# Logic_Engine_-_Front_SK6812.net
KiCad netlist of a schematic drawn in EAGLE
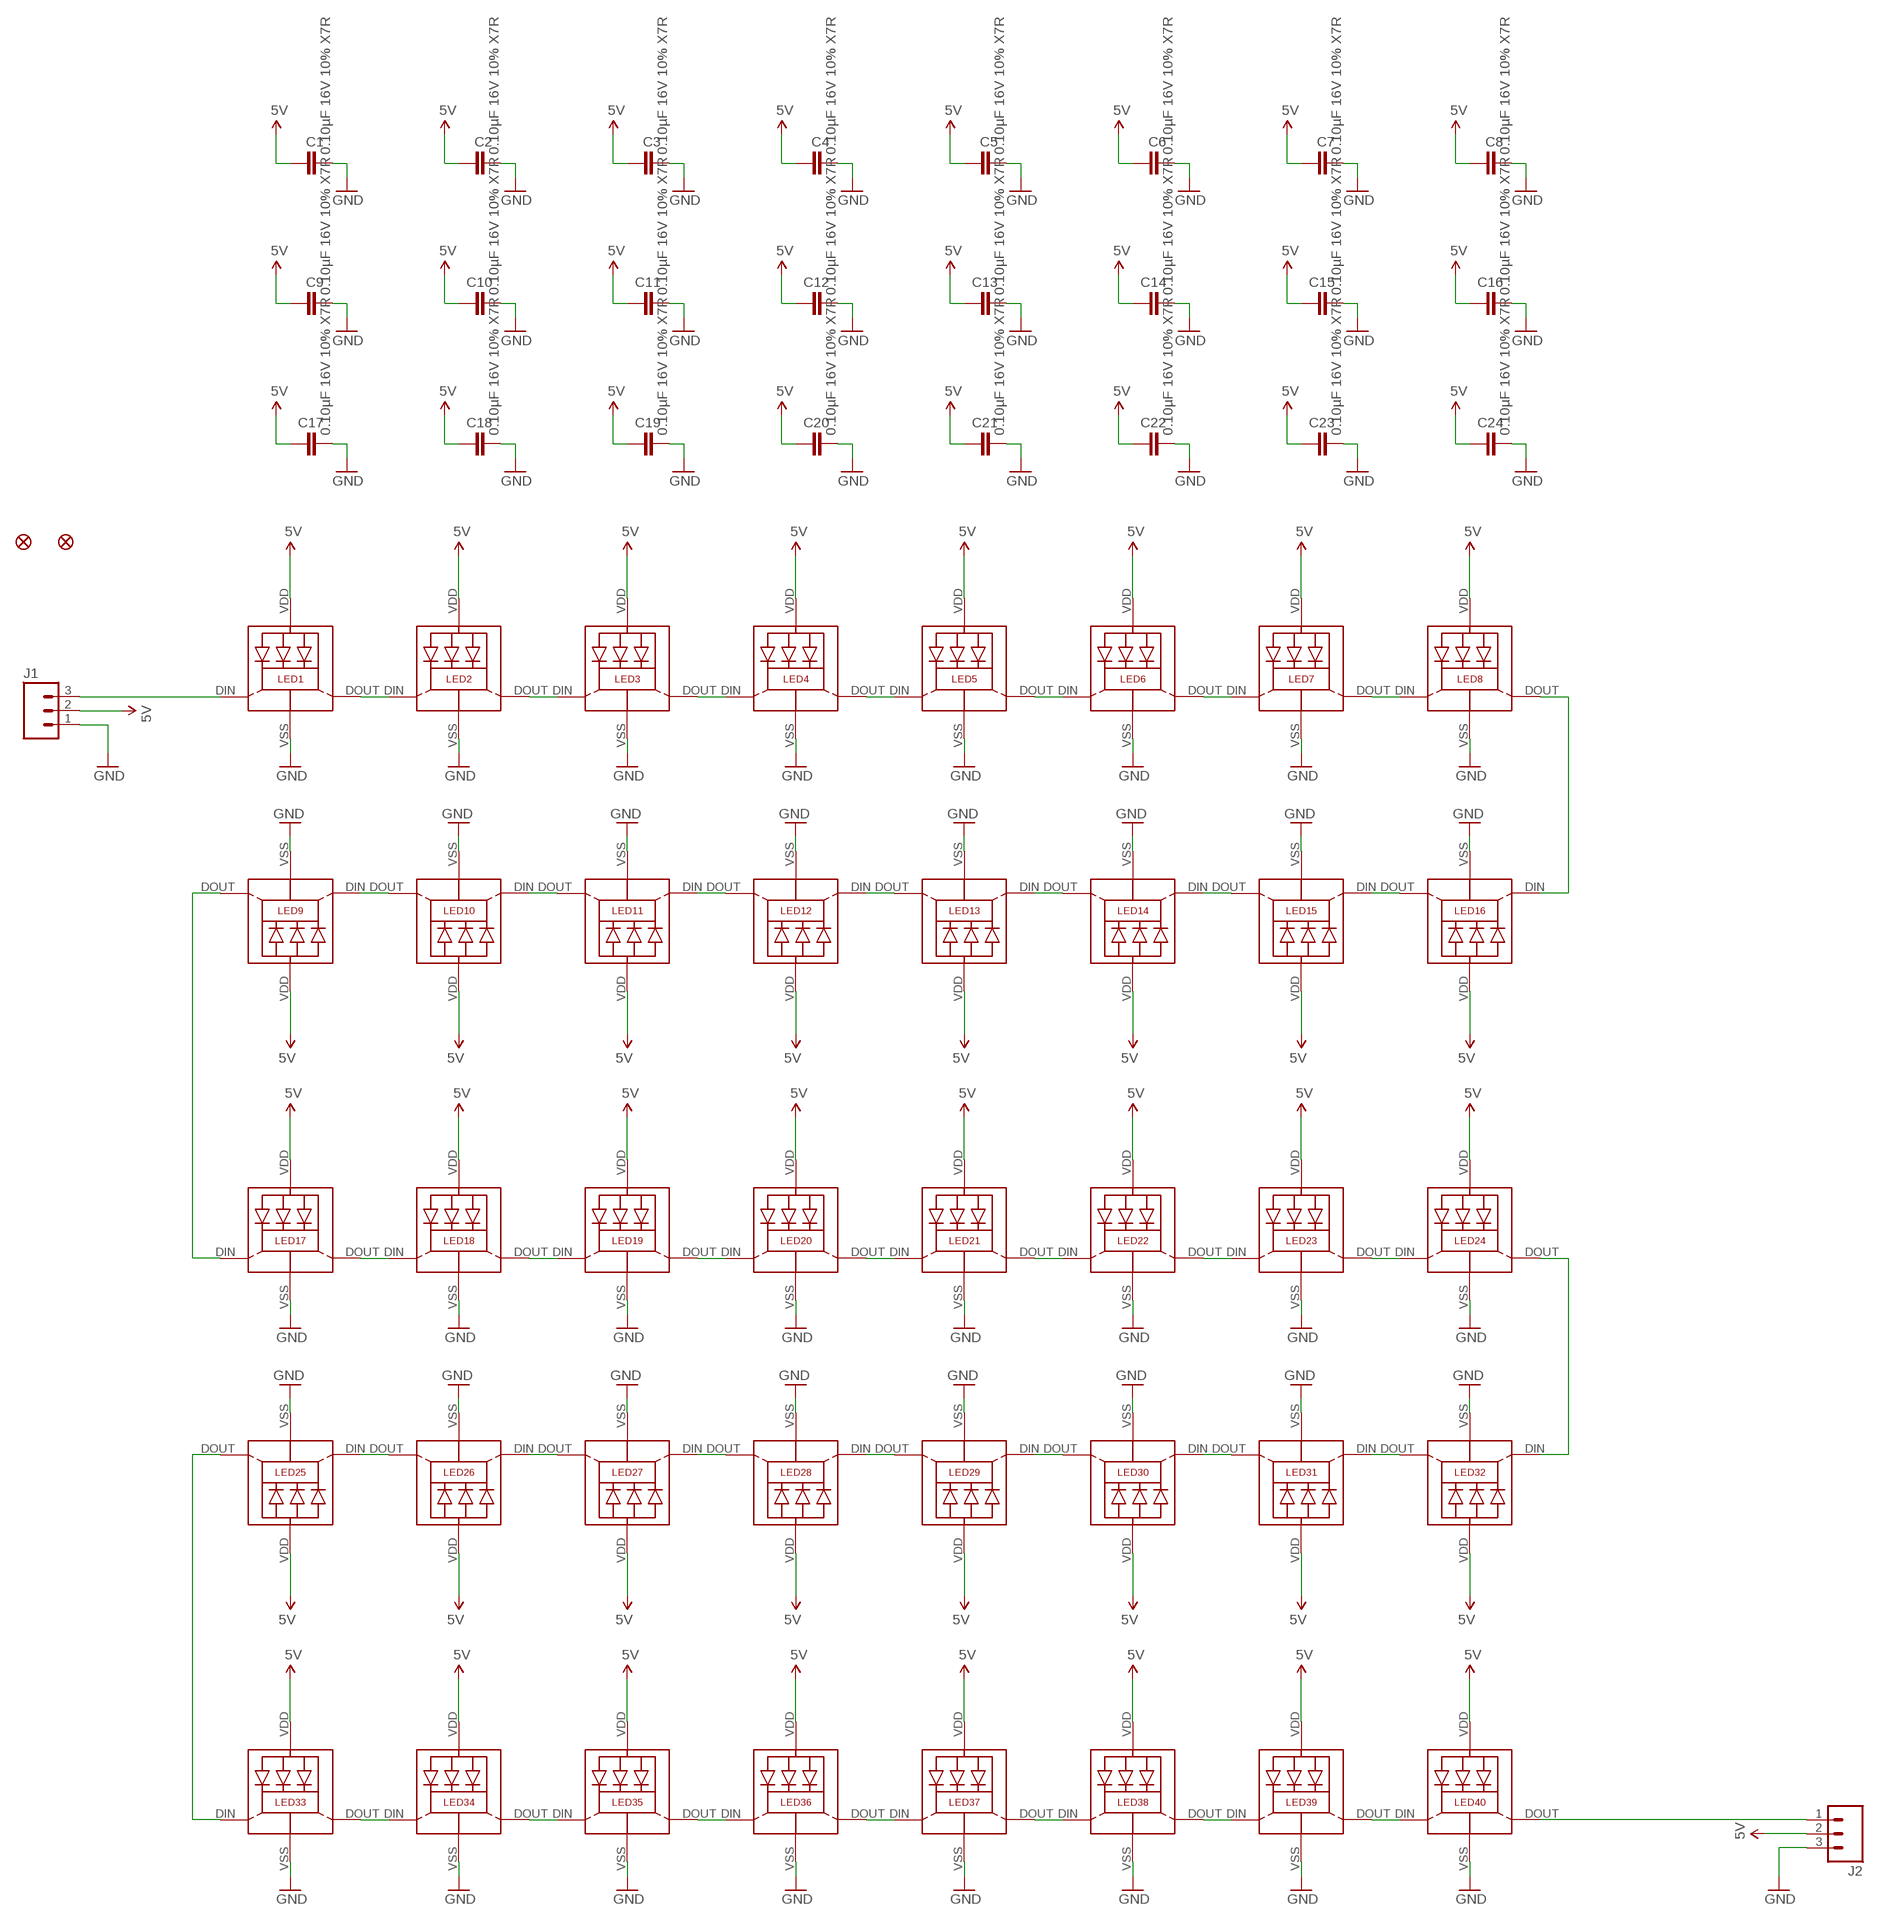
[diagram p0: schematic, sheet 1]

(export (version "E")
  (design (tool "Eeschema 10.0.6"))
  (components
    (comp (ref "C1")
      (value "0.10µF 16V 10% X7R")
      (footprint "eagle-import:C0603")
      (libsource (lib "eagle-import") (part "C-EUC0603"))
    )
    (comp (ref "C2")
      (value "0.10µF 16V 10% X7R")
      (footprint "eagle-import:C0603")
      (libsource (lib "eagle-import") (part "C-EUC0603"))
    )
    (comp (ref "C3")
      (value "0.10µF 16V 10% X7R")
      (footprint "eagle-import:C0603")
      (libsource (lib "eagle-import") (part "C-EUC0603"))
    )
    (comp (ref "C4")
      (value "0.10µF 16V 10% X7R")
      (footprint "eagle-import:C0603")
      (libsource (lib "eagle-import") (part "C-EUC0603"))
    )
    (comp (ref "C5")
      (value "0.10µF 16V 10% X7R")
      (footprint "eagle-import:C0603")
      (libsource (lib "eagle-import") (part "C-EUC0603"))
    )
    (comp (ref "C6")
      (value "0.10µF 16V 10% X7R")
      (footprint "eagle-import:C0603")
      (libsource (lib "eagle-import") (part "C-EUC0603"))
    )
    (comp (ref "C7")
      (value "0.10µF 16V 10% X7R")
      (footprint "eagle-import:C0603")
      (libsource (lib "eagle-import") (part "C-EUC0603"))
    )
    (comp (ref "C8")
      (value "0.10µF 16V 10% X7R")
      (footprint "eagle-import:C0603")
      (libsource (lib "eagle-import") (part "C-EUC0603"))
    )
    (comp (ref "C9")
      (value "0.10µF 16V 10% X7R")
      (footprint "eagle-import:C0603")
      (libsource (lib "eagle-import") (part "C-EUC0603"))
    )
    (comp (ref "C10")
      (value "0.10µF 16V 10% X7R")
      (footprint "eagle-import:C0603")
      (libsource (lib "eagle-import") (part "C-EUC0603"))
    )
    (comp (ref "C11")
      (value "0.10µF 16V 10% X7R")
      (footprint "eagle-import:C0603")
      (libsource (lib "eagle-import") (part "C-EUC0603"))
    )
    (comp (ref "C12")
      (value "0.10µF 16V 10% X7R")
      (footprint "eagle-import:C0603")
      (libsource (lib "eagle-import") (part "C-EUC0603"))
    )
    (comp (ref "C13")
      (value "0.10µF 16V 10% X7R")
      (footprint "eagle-import:C0603")
      (libsource (lib "eagle-import") (part "C-EUC0603"))
    )
    (comp (ref "C14")
      (value "0.10µF 16V 10% X7R")
      (footprint "eagle-import:C0603")
      (libsource (lib "eagle-import") (part "C-EUC0603"))
    )
    (comp (ref "C15")
      (value "0.10µF 16V 10% X7R")
      (footprint "eagle-import:C0603")
      (libsource (lib "eagle-import") (part "C-EUC0603"))
    )
    (comp (ref "C16")
      (value "0.10µF 16V 10% X7R")
      (footprint "eagle-import:C0603")
      (libsource (lib "eagle-import") (part "C-EUC0603"))
    )
    (comp (ref "C17")
      (value "0.10µF 16V 10% X7R")
      (footprint "eagle-import:C0603")
      (libsource (lib "eagle-import") (part "C-EUC0603"))
    )
    (comp (ref "C18")
      (value "0.10µF 16V 10% X7R")
      (footprint "eagle-import:C0603")
      (libsource (lib "eagle-import") (part "C-EUC0603"))
    )
    (comp (ref "C19")
      (value "0.10µF 16V 10% X7R")
      (footprint "eagle-import:C0603")
      (libsource (lib "eagle-import") (part "C-EUC0603"))
    )
    (comp (ref "C20")
      (value "0.10µF 16V 10% X7R")
      (footprint "eagle-import:C0603")
      (libsource (lib "eagle-import") (part "C-EUC0603"))
    )
    (comp (ref "C21")
      (value "0.10µF 16V 10% X7R")
      (footprint "eagle-import:C0603")
      (libsource (lib "eagle-import") (part "C-EUC0603"))
    )
    (comp (ref "C22")
      (value "0.10µF 16V 10% X7R")
      (footprint "eagle-import:C0603")
      (libsource (lib "eagle-import") (part "C-EUC0603"))
    )
    (comp (ref "C23")
      (value "0.10µF 16V 10% X7R")
      (footprint "eagle-import:C0603")
      (libsource (lib "eagle-import") (part "C-EUC0603"))
    )
    (comp (ref "C24")
      (value "0.10µF 16V 10% X7R")
      (footprint "eagle-import:C0603")
      (libsource (lib "eagle-import") (part "C-EUC0603"))
    )
    (comp (ref "FD1")
      (value "FIDUCIAL1X2")
      (footprint "eagle-import:FIDUCIAL-1X2")
      (libsource (lib "eagle-import") (part "FIDUCIAL1X2"))
    )
    (comp (ref "FD2")
      (value "FIDUCIAL1X2")
      (footprint "eagle-import:FIDUCIAL-1X2")
      (libsource (lib "eagle-import") (part "FIDUCIAL1X2"))
    )
    (comp (ref "J1")
      (value "M03PTH")
      (footprint "eagle-import:1X03")
      (libsource (lib "eagle-import") (part "M03PTH"))
    )
    (comp (ref "J2")
      (value "M03PTH")
      (footprint "eagle-import:1X03")
      (libsource (lib "eagle-import") (part "M03PTH"))
    )
    (comp (ref "LED1")
      (value "WS2812BSK6812MINI")
      (footprint "eagle-import:SK6812MINI")
      (libsource (lib "eagle-import") (part "WS2812BSK6812MINI"))
    )
    (comp (ref "LED2")
      (value "WS2812BSK6812MINI")
      (footprint "eagle-import:SK6812MINI")
      (libsource (lib "eagle-import") (part "WS2812BSK6812MINI"))
    )
    (comp (ref "LED3")
      (value "WS2812BSK6812MINI")
      (footprint "eagle-import:SK6812MINI")
      (libsource (lib "eagle-import") (part "WS2812BSK6812MINI"))
    )
    (comp (ref "LED4")
      (value "WS2812BSK6812MINI")
      (footprint "eagle-import:SK6812MINI")
      (libsource (lib "eagle-import") (part "WS2812BSK6812MINI"))
    )
    (comp (ref "LED5")
      (value "WS2812BSK6812MINI")
      (footprint "eagle-import:SK6812MINI")
      (libsource (lib "eagle-import") (part "WS2812BSK6812MINI"))
    )
    (comp (ref "LED6")
      (value "WS2812BSK6812MINI")
      (footprint "eagle-import:SK6812MINI")
      (libsource (lib "eagle-import") (part "WS2812BSK6812MINI"))
    )
    (comp (ref "LED7")
      (value "WS2812BSK6812MINI")
      (footprint "eagle-import:SK6812MINI")
      (libsource (lib "eagle-import") (part "WS2812BSK6812MINI"))
    )
    (comp (ref "LED8")
      (value "WS2812BSK6812MINI")
      (footprint "eagle-import:SK6812MINI")
      (libsource (lib "eagle-import") (part "WS2812BSK6812MINI"))
    )
    (comp (ref "LED9")
      (value "WS2812BSK6812MINI")
      (footprint "eagle-import:SK6812MINI")
      (libsource (lib "eagle-import") (part "WS2812BSK6812MINI"))
    )
    (comp (ref "LED10")
      (value "WS2812BSK6812MINI")
      (footprint "eagle-import:SK6812MINI")
      (libsource (lib "eagle-import") (part "WS2812BSK6812MINI"))
    )
    (comp (ref "LED11")
      (value "WS2812BSK6812MINI")
      (footprint "eagle-import:SK6812MINI")
      (libsource (lib "eagle-import") (part "WS2812BSK6812MINI"))
    )
    (comp (ref "LED12")
      (value "WS2812BSK6812MINI")
      (footprint "eagle-import:SK6812MINI")
      (libsource (lib "eagle-import") (part "WS2812BSK6812MINI"))
    )
    (comp (ref "LED13")
      (value "WS2812BSK6812MINI")
      (footprint "eagle-import:SK6812MINI")
      (libsource (lib "eagle-import") (part "WS2812BSK6812MINI"))
    )
    (comp (ref "LED14")
      (value "WS2812BSK6812MINI")
      (footprint "eagle-import:SK6812MINI")
      (libsource (lib "eagle-import") (part "WS2812BSK6812MINI"))
    )
    (comp (ref "LED15")
      (value "WS2812BSK6812MINI")
      (footprint "eagle-import:SK6812MINI")
      (libsource (lib "eagle-import") (part "WS2812BSK6812MINI"))
    )
    (comp (ref "LED16")
      (value "WS2812BSK6812MINI")
      (footprint "eagle-import:SK6812MINI")
      (libsource (lib "eagle-import") (part "WS2812BSK6812MINI"))
    )
    (comp (ref "LED17")
      (value "WS2812BSK6812MINI")
      (footprint "eagle-import:SK6812MINI")
      (libsource (lib "eagle-import") (part "WS2812BSK6812MINI"))
    )
    (comp (ref "LED18")
      (value "WS2812BSK6812MINI")
      (footprint "eagle-import:SK6812MINI")
      (libsource (lib "eagle-import") (part "WS2812BSK6812MINI"))
    )
    (comp (ref "LED19")
      (value "WS2812BSK6812MINI")
      (footprint "eagle-import:SK6812MINI")
      (libsource (lib "eagle-import") (part "WS2812BSK6812MINI"))
    )
    (comp (ref "LED20")
      (value "WS2812BSK6812MINI")
      (footprint "eagle-import:SK6812MINI")
      (libsource (lib "eagle-import") (part "WS2812BSK6812MINI"))
    )
    (comp (ref "LED21")
      (value "WS2812BSK6812MINI")
      (footprint "eagle-import:SK6812MINI")
      (libsource (lib "eagle-import") (part "WS2812BSK6812MINI"))
    )
    (comp (ref "LED22")
      (value "WS2812BSK6812MINI")
      (footprint "eagle-import:SK6812MINI")
      (libsource (lib "eagle-import") (part "WS2812BSK6812MINI"))
    )
    (comp (ref "LED23")
      (value "WS2812BSK6812MINI")
      (footprint "eagle-import:SK6812MINI")
      (libsource (lib "eagle-import") (part "WS2812BSK6812MINI"))
    )
    (comp (ref "LED24")
      (value "WS2812BSK6812MINI")
      (footprint "eagle-import:SK6812MINI")
      (libsource (lib "eagle-import") (part "WS2812BSK6812MINI"))
    )
    (comp (ref "LED25")
      (value "WS2812BSK6812MINI")
      (footprint "eagle-import:SK6812MINI")
      (libsource (lib "eagle-import") (part "WS2812BSK6812MINI"))
    )
    (comp (ref "LED26")
      (value "WS2812BSK6812MINI")
      (footprint "eagle-import:SK6812MINI")
      (libsource (lib "eagle-import") (part "WS2812BSK6812MINI"))
    )
    (comp (ref "LED27")
      (value "WS2812BSK6812MINI")
      (footprint "eagle-import:SK6812MINI")
      (libsource (lib "eagle-import") (part "WS2812BSK6812MINI"))
    )
    (comp (ref "LED28")
      (value "WS2812BSK6812MINI")
      (footprint "eagle-import:SK6812MINI")
      (libsource (lib "eagle-import") (part "WS2812BSK6812MINI"))
    )
    (comp (ref "LED29")
      (value "WS2812BSK6812MINI")
      (footprint "eagle-import:SK6812MINI")
      (libsource (lib "eagle-import") (part "WS2812BSK6812MINI"))
    )
    (comp (ref "LED30")
      (value "WS2812BSK6812MINI")
      (footprint "eagle-import:SK6812MINI")
      (libsource (lib "eagle-import") (part "WS2812BSK6812MINI"))
    )
    (comp (ref "LED31")
      (value "WS2812BSK6812MINI")
      (footprint "eagle-import:SK6812MINI")
      (libsource (lib "eagle-import") (part "WS2812BSK6812MINI"))
    )
    (comp (ref "LED32")
      (value "WS2812BSK6812MINI")
      (footprint "eagle-import:SK6812MINI")
      (libsource (lib "eagle-import") (part "WS2812BSK6812MINI"))
    )
    (comp (ref "LED33")
      (value "WS2812BSK6812MINI")
      (footprint "eagle-import:SK6812MINI")
      (libsource (lib "eagle-import") (part "WS2812BSK6812MINI"))
    )
    (comp (ref "LED34")
      (value "WS2812BSK6812MINI")
      (footprint "eagle-import:SK6812MINI")
      (libsource (lib "eagle-import") (part "WS2812BSK6812MINI"))
    )
    (comp (ref "LED35")
      (value "WS2812BSK6812MINI")
      (footprint "eagle-import:SK6812MINI")
      (libsource (lib "eagle-import") (part "WS2812BSK6812MINI"))
    )
    (comp (ref "LED36")
      (value "WS2812BSK6812MINI")
      (footprint "eagle-import:SK6812MINI")
      (libsource (lib "eagle-import") (part "WS2812BSK6812MINI"))
    )
    (comp (ref "LED37")
      (value "WS2812BSK6812MINI")
      (footprint "eagle-import:SK6812MINI")
      (libsource (lib "eagle-import") (part "WS2812BSK6812MINI"))
    )
    (comp (ref "LED38")
      (value "WS2812BSK6812MINI")
      (footprint "eagle-import:SK6812MINI")
      (libsource (lib "eagle-import") (part "WS2812BSK6812MINI"))
    )
    (comp (ref "LED39")
      (value "WS2812BSK6812MINI")
      (footprint "eagle-import:SK6812MINI")
      (libsource (lib "eagle-import") (part "WS2812BSK6812MINI"))
    )
    (comp (ref "LED40")
      (value "WS2812BSK6812MINI")
      (footprint "eagle-import:SK6812MINI")
      (libsource (lib "eagle-import") (part "WS2812BSK6812MINI"))
    )
  )
  (nets
    (net (code "1") (name "5V") (class "Default")
      (node (ref "C1") (pin "1") (pinfunction "1_1") (pintype "passive"))
      (node (ref "C10") (pin "1") (pinfunction "1_1") (pintype "passive"))
      (node (ref "C11") (pin "1") (pinfunction "1_1") (pintype "passive"))
      (node (ref "C12") (pin "1") (pinfunction "1_1") (pintype "passive"))
      (node (ref "C13") (pin "1") (pinfunction "1_1") (pintype "passive"))
      (node (ref "C14") (pin "1") (pinfunction "1_1") (pintype "passive"))
      (node (ref "C15") (pin "1") (pinfunction "1_1") (pintype "passive"))
      (node (ref "C16") (pin "1") (pinfunction "1_1") (pintype "passive"))
      (node (ref "C17") (pin "1") (pinfunction "1_1") (pintype "passive"))
      (node (ref "C18") (pin "1") (pinfunction "1_1") (pintype "passive"))
      (node (ref "C19") (pin "1") (pinfunction "1_1") (pintype "passive"))
      (node (ref "C2") (pin "1") (pinfunction "1_1") (pintype "passive"))
      (node (ref "C20") (pin "1") (pinfunction "1_1") (pintype "passive"))
      (node (ref "C21") (pin "1") (pinfunction "1_1") (pintype "passive"))
      (node (ref "C22") (pin "1") (pinfunction "1_1") (pintype "passive"))
      (node (ref "C23") (pin "1") (pinfunction "1_1") (pintype "passive"))
      (node (ref "C24") (pin "1") (pinfunction "1_1") (pintype "passive"))
      (node (ref "C3") (pin "1") (pinfunction "1_1") (pintype "passive"))
      (node (ref "C4") (pin "1") (pinfunction "1_1") (pintype "passive"))
      (node (ref "C5") (pin "1") (pinfunction "1_1") (pintype "passive"))
      (node (ref "C6") (pin "1") (pinfunction "1_1") (pintype "passive"))
      (node (ref "C7") (pin "1") (pinfunction "1_1") (pintype "passive"))
      (node (ref "C8") (pin "1") (pinfunction "1_1") (pintype "passive"))
      (node (ref "C9") (pin "1") (pinfunction "1_1") (pintype "passive"))
      (node (ref "J1") (pin "2") (pinfunction "2_2") (pintype "passive"))
      (node (ref "J2") (pin "2") (pinfunction "2_2") (pintype "passive"))
      (node (ref "LED1") (pin "VDD") (pinfunction "VDD_VDD") (pintype "power_in"))
      (node (ref "LED10") (pin "VDD") (pinfunction "VDD_VDD") (pintype "power_in"))
      (node (ref "LED11") (pin "VDD") (pinfunction "VDD_VDD") (pintype "power_in"))
      (node (ref "LED12") (pin "VDD") (pinfunction "VDD_VDD") (pintype "power_in"))
      (node (ref "LED13") (pin "VDD") (pinfunction "VDD_VDD") (pintype "power_in"))
      (node (ref "LED14") (pin "VDD") (pinfunction "VDD_VDD") (pintype "power_in"))
      (node (ref "LED15") (pin "VDD") (pinfunction "VDD_VDD") (pintype "power_in"))
      (node (ref "LED16") (pin "VDD") (pinfunction "VDD_VDD") (pintype "power_in"))
      (node (ref "LED17") (pin "VDD") (pinfunction "VDD_VDD") (pintype "power_in"))
      (node (ref "LED18") (pin "VDD") (pinfunction "VDD_VDD") (pintype "power_in"))
      (node (ref "LED19") (pin "VDD") (pinfunction "VDD_VDD") (pintype "power_in"))
      (node (ref "LED2") (pin "VDD") (pinfunction "VDD_VDD") (pintype "power_in"))
      (node (ref "LED20") (pin "VDD") (pinfunction "VDD_VDD") (pintype "power_in"))
      (node (ref "LED21") (pin "VDD") (pinfunction "VDD_VDD") (pintype "power_in"))
      (node (ref "LED22") (pin "VDD") (pinfunction "VDD_VDD") (pintype "power_in"))
      (node (ref "LED23") (pin "VDD") (pinfunction "VDD_VDD") (pintype "power_in"))
      (node (ref "LED24") (pin "VDD") (pinfunction "VDD_VDD") (pintype "power_in"))
      (node (ref "LED25") (pin "VDD") (pinfunction "VDD_VDD") (pintype "power_in"))
      (node (ref "LED26") (pin "VDD") (pinfunction "VDD_VDD") (pintype "power_in"))
      (node (ref "LED27") (pin "VDD") (pinfunction "VDD_VDD") (pintype "power_in"))
      (node (ref "LED28") (pin "VDD") (pinfunction "VDD_VDD") (pintype "power_in"))
      (node (ref "LED29") (pin "VDD") (pinfunction "VDD_VDD") (pintype "power_in"))
      (node (ref "LED3") (pin "VDD") (pinfunction "VDD_VDD") (pintype "power_in"))
      (node (ref "LED30") (pin "VDD") (pinfunction "VDD_VDD") (pintype "power_in"))
      (node (ref "LED31") (pin "VDD") (pinfunction "VDD_VDD") (pintype "power_in"))
      (node (ref "LED32") (pin "VDD") (pinfunction "VDD_VDD") (pintype "power_in"))
      (node (ref "LED33") (pin "VDD") (pinfunction "VDD_VDD") (pintype "power_in"))
      (node (ref "LED34") (pin "VDD") (pinfunction "VDD_VDD") (pintype "power_in"))
      (node (ref "LED35") (pin "VDD") (pinfunction "VDD_VDD") (pintype "power_in"))
      (node (ref "LED36") (pin "VDD") (pinfunction "VDD_VDD") (pintype "power_in"))
      (node (ref "LED37") (pin "VDD") (pinfunction "VDD_VDD") (pintype "power_in"))
      (node (ref "LED38") (pin "VDD") (pinfunction "VDD_VDD") (pintype "power_in"))
      (node (ref "LED39") (pin "VDD") (pinfunction "VDD_VDD") (pintype "power_in"))
      (node (ref "LED4") (pin "VDD") (pinfunction "VDD_VDD") (pintype "power_in"))
      (node (ref "LED40") (pin "VDD") (pinfunction "VDD_VDD") (pintype "power_in"))
      (node (ref "LED5") (pin "VDD") (pinfunction "VDD_VDD") (pintype "power_in"))
      (node (ref "LED6") (pin "VDD") (pinfunction "VDD_VDD") (pintype "power_in"))
      (node (ref "LED7") (pin "VDD") (pinfunction "VDD_VDD") (pintype "power_in"))
      (node (ref "LED8") (pin "VDD") (pinfunction "VDD_VDD") (pintype "power_in"))
      (node (ref "LED9") (pin "VDD") (pinfunction "VDD_VDD") (pintype "power_in"))
    )
    (net (code "2") (name "GND") (class "Default")
      (node (ref "C1") (pin "2") (pinfunction "2_2") (pintype "passive"))
      (node (ref "C10") (pin "2") (pinfunction "2_2") (pintype "passive"))
      (node (ref "C11") (pin "2") (pinfunction "2_2") (pintype "passive"))
      (node (ref "C12") (pin "2") (pinfunction "2_2") (pintype "passive"))
      (node (ref "C13") (pin "2") (pinfunction "2_2") (pintype "passive"))
      (node (ref "C14") (pin "2") (pinfunction "2_2") (pintype "passive"))
      (node (ref "C15") (pin "2") (pinfunction "2_2") (pintype "passive"))
      (node (ref "C16") (pin "2") (pinfunction "2_2") (pintype "passive"))
      (node (ref "C17") (pin "2") (pinfunction "2_2") (pintype "passive"))
      (node (ref "C18") (pin "2") (pinfunction "2_2") (pintype "passive"))
      (node (ref "C19") (pin "2") (pinfunction "2_2") (pintype "passive"))
      (node (ref "C2") (pin "2") (pinfunction "2_2") (pintype "passive"))
      (node (ref "C20") (pin "2") (pinfunction "2_2") (pintype "passive"))
      (node (ref "C21") (pin "2") (pinfunction "2_2") (pintype "passive"))
      (node (ref "C22") (pin "2") (pinfunction "2_2") (pintype "passive"))
      (node (ref "C23") (pin "2") (pinfunction "2_2") (pintype "passive"))
      (node (ref "C24") (pin "2") (pinfunction "2_2") (pintype "passive"))
      (node (ref "C3") (pin "2") (pinfunction "2_2") (pintype "passive"))
      (node (ref "C4") (pin "2") (pinfunction "2_2") (pintype "passive"))
      (node (ref "C5") (pin "2") (pinfunction "2_2") (pintype "passive"))
      (node (ref "C6") (pin "2") (pinfunction "2_2") (pintype "passive"))
      (node (ref "C7") (pin "2") (pinfunction "2_2") (pintype "passive"))
      (node (ref "C8") (pin "2") (pinfunction "2_2") (pintype "passive"))
      (node (ref "C9") (pin "2") (pinfunction "2_2") (pintype "passive"))
      (node (ref "J1") (pin "1") (pinfunction "1_1") (pintype "passive"))
      (node (ref "J2") (pin "3") (pinfunction "3_3") (pintype "passive"))
      (node (ref "LED1") (pin "VSS") (pinfunction "GND_VSS") (pintype "power_in"))
      (node (ref "LED10") (pin "VSS") (pinfunction "GND_VSS") (pintype "power_in"))
      (node (ref "LED11") (pin "VSS") (pinfunction "GND_VSS") (pintype "power_in"))
      (node (ref "LED12") (pin "VSS") (pinfunction "GND_VSS") (pintype "power_in"))
      (node (ref "LED13") (pin "VSS") (pinfunction "GND_VSS") (pintype "power_in"))
      (node (ref "LED14") (pin "VSS") (pinfunction "GND_VSS") (pintype "power_in"))
      (node (ref "LED15") (pin "VSS") (pinfunction "GND_VSS") (pintype "power_in"))
      (node (ref "LED16") (pin "VSS") (pinfunction "GND_VSS") (pintype "power_in"))
      (node (ref "LED17") (pin "VSS") (pinfunction "GND_VSS") (pintype "power_in"))
      (node (ref "LED18") (pin "VSS") (pinfunction "GND_VSS") (pintype "power_in"))
      (node (ref "LED19") (pin "VSS") (pinfunction "GND_VSS") (pintype "power_in"))
      (node (ref "LED2") (pin "VSS") (pinfunction "GND_VSS") (pintype "power_in"))
      (node (ref "LED20") (pin "VSS") (pinfunction "GND_VSS") (pintype "power_in"))
      (node (ref "LED21") (pin "VSS") (pinfunction "GND_VSS") (pintype "power_in"))
      (node (ref "LED22") (pin "VSS") (pinfunction "GND_VSS") (pintype "power_in"))
      (node (ref "LED23") (pin "VSS") (pinfunction "GND_VSS") (pintype "power_in"))
      (node (ref "LED24") (pin "VSS") (pinfunction "GND_VSS") (pintype "power_in"))
      (node (ref "LED25") (pin "VSS") (pinfunction "GND_VSS") (pintype "power_in"))
      (node (ref "LED26") (pin "VSS") (pinfunction "GND_VSS") (pintype "power_in"))
      (node (ref "LED27") (pin "VSS") (pinfunction "GND_VSS") (pintype "power_in"))
      (node (ref "LED28") (pin "VSS") (pinfunction "GND_VSS") (pintype "power_in"))
      (node (ref "LED29") (pin "VSS") (pinfunction "GND_VSS") (pintype "power_in"))
      (node (ref "LED3") (pin "VSS") (pinfunction "GND_VSS") (pintype "power_in"))
      (node (ref "LED30") (pin "VSS") (pinfunction "GND_VSS") (pintype "power_in"))
      (node (ref "LED31") (pin "VSS") (pinfunction "GND_VSS") (pintype "power_in"))
      (node (ref "LED32") (pin "VSS") (pinfunction "GND_VSS") (pintype "power_in"))
      (node (ref "LED33") (pin "VSS") (pinfunction "GND_VSS") (pintype "power_in"))
      (node (ref "LED34") (pin "VSS") (pinfunction "GND_VSS") (pintype "power_in"))
      (node (ref "LED35") (pin "VSS") (pinfunction "GND_VSS") (pintype "power_in"))
      (node (ref "LED36") (pin "VSS") (pinfunction "GND_VSS") (pintype "power_in"))
      (node (ref "LED37") (pin "VSS") (pinfunction "GND_VSS") (pintype "power_in"))
      (node (ref "LED38") (pin "VSS") (pinfunction "GND_VSS") (pintype "power_in"))
      (node (ref "LED39") (pin "VSS") (pinfunction "GND_VSS") (pintype "power_in"))
      (node (ref "LED4") (pin "VSS") (pinfunction "GND_VSS") (pintype "power_in"))
      (node (ref "LED40") (pin "VSS") (pinfunction "GND_VSS") (pintype "power_in"))
      (node (ref "LED5") (pin "VSS") (pinfunction "GND_VSS") (pintype "power_in"))
      (node (ref "LED6") (pin "VSS") (pinfunction "GND_VSS") (pintype "power_in"))
      (node (ref "LED7") (pin "VSS") (pinfunction "GND_VSS") (pintype "power_in"))
      (node (ref "LED8") (pin "VSS") (pinfunction "GND_VSS") (pintype "power_in"))
      (node (ref "LED9") (pin "VSS") (pinfunction "GND_VSS") (pintype "power_in"))
    )
    (net (code "3") (name "Net-(LED1-DI)") (class "Default")
      (node (ref "J1") (pin "3") (pinfunction "3_3") (pintype "passive"))
      (node (ref "LED1") (pin "DIN") (pinfunction "DI_DIN") (pintype "input"))
    )
    (net (code "4") (name "Net-(LED1-DO)") (class "Default")
      (node (ref "LED1") (pin "DOUT") (pinfunction "DO_DOUT") (pintype "output"))
      (node (ref "LED2") (pin "DIN") (pinfunction "DI_DIN") (pintype "input"))
    )
    (net (code "5") (name "Net-(LED2-DO)") (class "Default")
      (node (ref "LED2") (pin "DOUT") (pinfunction "DO_DOUT") (pintype "output"))
      (node (ref "LED3") (pin "DIN") (pinfunction "DI_DIN") (pintype "input"))
    )
    (net (code "6") (name "Net-(LED3-DO)") (class "Default")
      (node (ref "LED3") (pin "DOUT") (pinfunction "DO_DOUT") (pintype "output"))
      (node (ref "LED4") (pin "DIN") (pinfunction "DI_DIN") (pintype "input"))
    )
    (net (code "7") (name "Net-(LED4-DO)") (class "Default")
      (node (ref "LED4") (pin "DOUT") (pinfunction "DO_DOUT") (pintype "output"))
      (node (ref "LED5") (pin "DIN") (pinfunction "DI_DIN") (pintype "input"))
    )
    (net (code "8") (name "Net-(LED5-DO)") (class "Default")
      (node (ref "LED5") (pin "DOUT") (pinfunction "DO_DOUT") (pintype "output"))
      (node (ref "LED6") (pin "DIN") (pinfunction "DI_DIN") (pintype "input"))
    )
    (net (code "9") (name "Net-(LED6-DO)") (class "Default")
      (node (ref "LED6") (pin "DOUT") (pinfunction "DO_DOUT") (pintype "output"))
      (node (ref "LED7") (pin "DIN") (pinfunction "DI_DIN") (pintype "input"))
    )
    (net (code "10") (name "Net-(LED7-DO)") (class "Default")
      (node (ref "LED7") (pin "DOUT") (pinfunction "DO_DOUT") (pintype "output"))
      (node (ref "LED8") (pin "DIN") (pinfunction "DI_DIN") (pintype "input"))
    )
    (net (code "11") (name "Net-(LED10-DI)") (class "Default")
      (node (ref "LED10") (pin "DIN") (pinfunction "DI_DIN") (pintype "input"))
      (node (ref "LED11") (pin "DOUT") (pinfunction "DO_DOUT") (pintype "output"))
    )
    (net (code "12") (name "Net-(LED10-DO)") (class "Default")
      (node (ref "LED10") (pin "DOUT") (pinfunction "DO_DOUT") (pintype "output"))
      (node (ref "LED9") (pin "DIN") (pinfunction "DI_DIN") (pintype "input"))
    )
    (net (code "13") (name "Net-(LED11-DI)") (class "Default")
      (node (ref "LED11") (pin "DIN") (pinfunction "DI_DIN") (pintype "input"))
      (node (ref "LED12") (pin "DOUT") (pinfunction "DO_DOUT") (pintype "output"))
    )
    (net (code "14") (name "Net-(LED12-DI)") (class "Default")
      (node (ref "LED12") (pin "DIN") (pinfunction "DI_DIN") (pintype "input"))
      (node (ref "LED13") (pin "DOUT") (pinfunction "DO_DOUT") (pintype "output"))
    )
    (net (code "15") (name "Net-(LED13-DI)") (class "Default")
      (node (ref "LED13") (pin "DIN") (pinfunction "DI_DIN") (pintype "input"))
      (node (ref "LED14") (pin "DOUT") (pinfunction "DO_DOUT") (pintype "output"))
    )
    (net (code "16") (name "Net-(LED14-DI)") (class "Default")
      (node (ref "LED14") (pin "DIN") (pinfunction "DI_DIN") (pintype "input"))
      (node (ref "LED15") (pin "DOUT") (pinfunction "DO_DOUT") (pintype "output"))
    )
    (net (code "17") (name "Net-(LED15-DI)") (class "Default")
      (node (ref "LED15") (pin "DIN") (pinfunction "DI_DIN") (pintype "input"))
      (node (ref "LED16") (pin "DOUT") (pinfunction "DO_DOUT") (pintype "output"))
    )
    (net (code "18") (name "Net-(LED16-DI)") (class "Default")
      (node (ref "LED16") (pin "DIN") (pinfunction "DI_DIN") (pintype "input"))
      (node (ref "LED8") (pin "DOUT") (pinfunction "DO_DOUT") (pintype "output"))
    )
    (net (code "19") (name "Net-(LED17-DI)") (class "Default")
      (node (ref "LED17") (pin "DIN") (pinfunction "DI_DIN") (pintype "input"))
      (node (ref "LED9") (pin "DOUT") (pinfunction "DO_DOUT") (pintype "output"))
    )
    (net (code "20") (name "Net-(LED17-DO)") (class "Default")
      (node (ref "LED17") (pin "DOUT") (pinfunction "DO_DOUT") (pintype "output"))
      (node (ref "LED18") (pin "DIN") (pinfunction "DI_DIN") (pintype "input"))
    )
    (net (code "21") (name "Net-(LED18-DO)") (class "Default")
      (node (ref "LED18") (pin "DOUT") (pinfunction "DO_DOUT") (pintype "output"))
      (node (ref "LED19") (pin "DIN") (pinfunction "DI_DIN") (pintype "input"))
    )
    (net (code "22") (name "Net-(LED19-DO)") (class "Default")
      (node (ref "LED19") (pin "DOUT") (pinfunction "DO_DOUT") (pintype "output"))
      (node (ref "LED20") (pin "DIN") (pinfunction "DI_DIN") (pintype "input"))
    )
    (net (code "23") (name "Net-(LED20-DO)") (class "Default")
      (node (ref "LED20") (pin "DOUT") (pinfunction "DO_DOUT") (pintype "output"))
      (node (ref "LED21") (pin "DIN") (pinfunction "DI_DIN") (pintype "input"))
    )
    (net (code "24") (name "Net-(LED21-DO)") (class "Default")
      (node (ref "LED21") (pin "DOUT") (pinfunction "DO_DOUT") (pintype "output"))
      (node (ref "LED22") (pin "DIN") (pinfunction "DI_DIN") (pintype "input"))
    )
    (net (code "25") (name "Net-(LED22-DO)") (class "Default")
      (node (ref "LED22") (pin "DOUT") (pinfunction "DO_DOUT") (pintype "output"))
      (node (ref "LED23") (pin "DIN") (pinfunction "DI_DIN") (pintype "input"))
    )
    (net (code "26") (name "Net-(LED23-DO)") (class "Default")
      (node (ref "LED23") (pin "DOUT") (pinfunction "DO_DOUT") (pintype "output"))
      (node (ref "LED24") (pin "DIN") (pinfunction "DI_DIN") (pintype "input"))
    )
    (net (code "27") (name "Net-(LED24-DO)") (class "Default")
      (node (ref "LED24") (pin "DOUT") (pinfunction "DO_DOUT") (pintype "output"))
      (node (ref "LED32") (pin "DIN") (pinfunction "DI_DIN") (pintype "input"))
    )
    (net (code "28") (name "Net-(LED25-DI)") (class "Default")
      (node (ref "LED25") (pin "DIN") (pinfunction "DI_DIN") (pintype "input"))
      (node (ref "LED26") (pin "DOUT") (pinfunction "DO_DOUT") (pintype "output"))
    )
    (net (code "29") (name "Net-(LED25-DO)") (class "Default")
      (node (ref "LED25") (pin "DOUT") (pinfunction "DO_DOUT") (pintype "output"))
      (node (ref "LED33") (pin "DIN") (pinfunction "DI_DIN") (pintype "input"))
    )
    (net (code "30") (name "Net-(LED26-DI)") (class "Default")
      (node (ref "LED26") (pin "DIN") (pinfunction "DI_DIN") (pintype "input"))
      (node (ref "LED27") (pin "DOUT") (pinfunction "DO_DOUT") (pintype "output"))
    )
    (net (code "31") (name "Net-(LED27-DI)") (class "Default")
      (node (ref "LED27") (pin "DIN") (pinfunction "DI_DIN") (pintype "input"))
      (node (ref "LED28") (pin "DOUT") (pinfunction "DO_DOUT") (pintype "output"))
    )
    (net (code "32") (name "Net-(LED28-DI)") (class "Default")
      (node (ref "LED28") (pin "DIN") (pinfunction "DI_DIN") (pintype "input"))
      (node (ref "LED29") (pin "DOUT") (pinfunction "DO_DOUT") (pintype "output"))
    )
    (net (code "33") (name "Net-(LED29-DI)") (class "Default")
      (node (ref "LED29") (pin "DIN") (pinfunction "DI_DIN") (pintype "input"))
      (node (ref "LED30") (pin "DOUT") (pinfunction "DO_DOUT") (pintype "output"))
    )
    (net (code "34") (name "Net-(LED30-DI)") (class "Default")
      (node (ref "LED30") (pin "DIN") (pinfunction "DI_DIN") (pintype "input"))
      (node (ref "LED31") (pin "DOUT") (pinfunction "DO_DOUT") (pintype "output"))
    )
    (net (code "35") (name "Net-(LED31-DI)") (class "Default")
      (node (ref "LED31") (pin "DIN") (pinfunction "DI_DIN") (pintype "input"))
      (node (ref "LED32") (pin "DOUT") (pinfunction "DO_DOUT") (pintype "output"))
    )
    (net (code "36") (name "Net-(LED33-DO)") (class "Default")
      (node (ref "LED33") (pin "DOUT") (pinfunction "DO_DOUT") (pintype "output"))
      (node (ref "LED34") (pin "DIN") (pinfunction "DI_DIN") (pintype "input"))
    )
    (net (code "37") (name "Net-(LED34-DO)") (class "Default")
      (node (ref "LED34") (pin "DOUT") (pinfunction "DO_DOUT") (pintype "output"))
      (node (ref "LED35") (pin "DIN") (pinfunction "DI_DIN") (pintype "input"))
    )
    (net (code "38") (name "Net-(LED35-DO)") (class "Default")
      (node (ref "LED35") (pin "DOUT") (pinfunction "DO_DOUT") (pintype "output"))
      (node (ref "LED36") (pin "DIN") (pinfunction "DI_DIN") (pintype "input"))
    )
    (net (code "39") (name "Net-(LED36-DO)") (class "Default")
      (node (ref "LED36") (pin "DOUT") (pinfunction "DO_DOUT") (pintype "output"))
      (node (ref "LED37") (pin "DIN") (pinfunction "DI_DIN") (pintype "input"))
    )
    (net (code "40") (name "Net-(LED37-DO)") (class "Default")
      (node (ref "LED37") (pin "DOUT") (pinfunction "DO_DOUT") (pintype "output"))
      (node (ref "LED38") (pin "DIN") (pinfunction "DI_DIN") (pintype "input"))
    )
    (net (code "41") (name "Net-(LED38-DO)") (class "Default")
      (node (ref "LED38") (pin "DOUT") (pinfunction "DO_DOUT") (pintype "output"))
      (node (ref "LED39") (pin "DIN") (pinfunction "DI_DIN") (pintype "input"))
    )
    (net (code "42") (name "Net-(LED39-DO)") (class "Default")
      (node (ref "LED39") (pin "DOUT") (pinfunction "DO_DOUT") (pintype "output"))
      (node (ref "LED40") (pin "DIN") (pinfunction "DI_DIN") (pintype "input"))
    )
    (net (code "43") (name "Net-(LED40-DO)") (class "Default")
      (node (ref "J2") (pin "1") (pinfunction "1_1") (pintype "passive"))
      (node (ref "LED40") (pin "DOUT") (pinfunction "DO_DOUT") (pintype "output"))
    )
  )
)
